# HorsPCB.net
KiCad netlist of a schematic drawn in Altium Designer
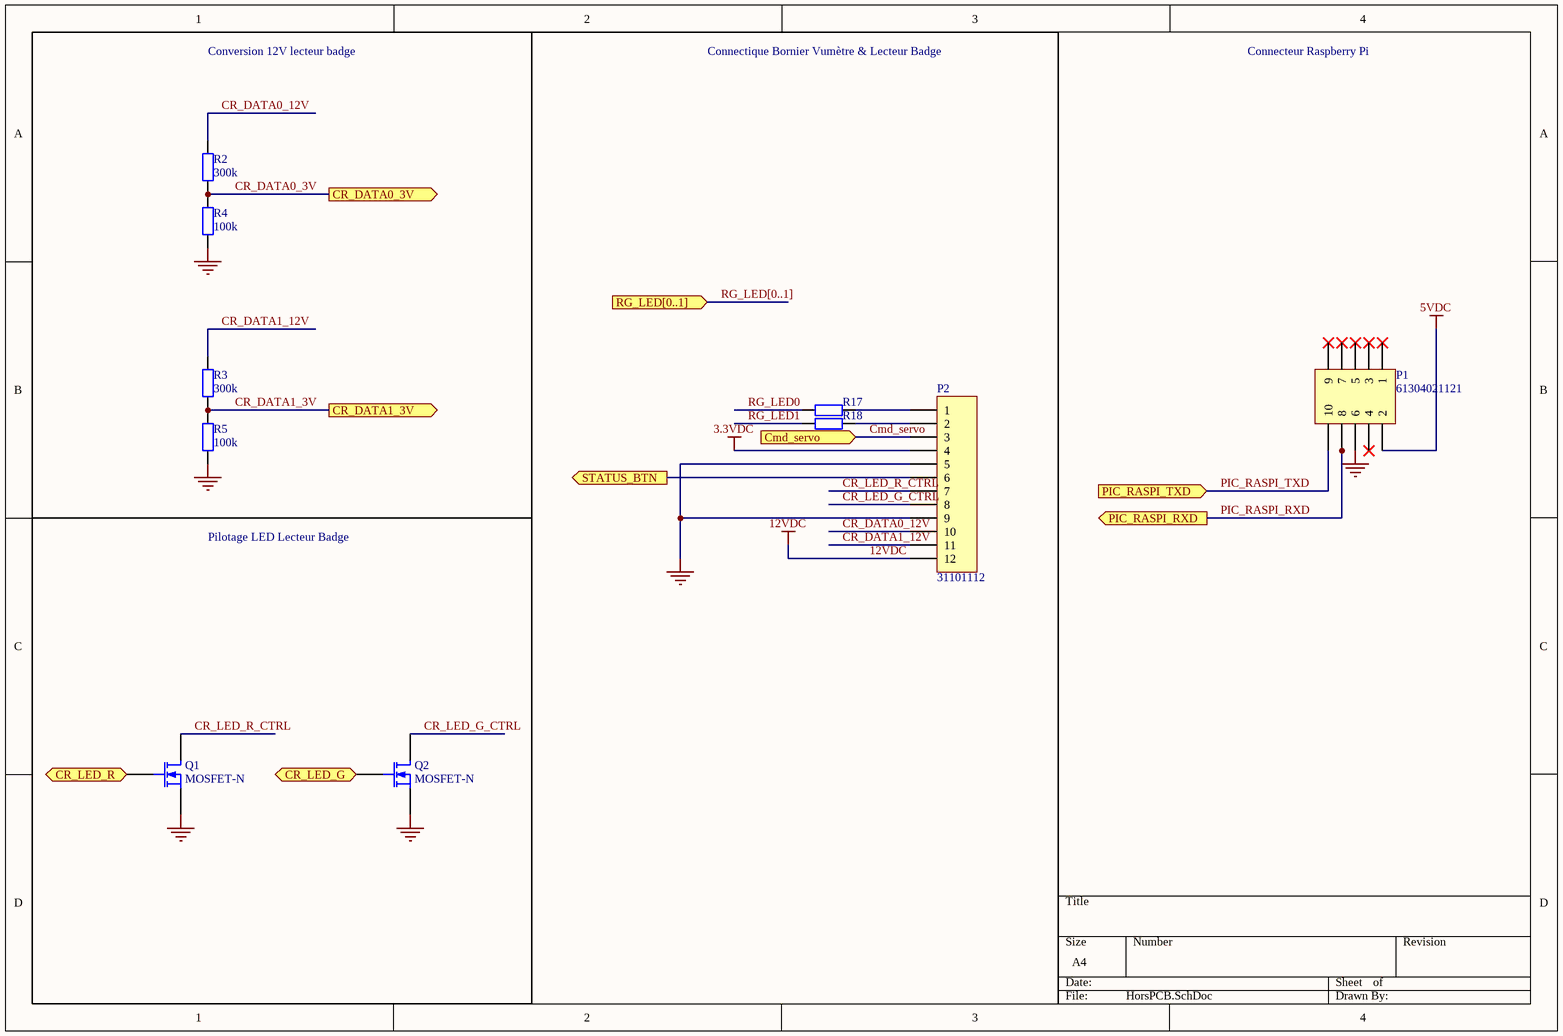
[diagram p0: HorsPCB.SchDoc]

(export (version "E")
  (design (tool "Eeschema 10.0.6"))
  (components
    (comp (ref "P1")
      (value "61304021121")
      (footprint "HDR2X5")
      (description "Header, 5-Pin, Dual row")
      (libsource (lib "Miscellaneous Connectors") (part "Header 5X2"))
    )
    (comp (ref "P2")
      (value "31101112")
      (footprint "Bornier12")
      (description "Header, 12-Pin")
      (libsource (lib "Miscellaneous Connectors") (part "Header 12"))
    )
    (comp (ref "Q1")
      (value "MOSFET-N")
      (footprint "nouveau_mosfetN")
      (description "N-Channel MOSFET")
      (libsource (lib "Miscellaneous Devices") (part "MOSFET-N"))
    )
    (comp (ref "Q2")
      (value "MOSFET-N")
      (footprint "nouveau_mosfetN")
      (description "N-Channel MOSFET")
      (libsource (lib "Miscellaneous Devices") (part "MOSFET-N"))
    )
    (comp (ref "R2")
      (value "300k")
      (footprint "0603")
      (description "Resistor")
      (libsource (lib "Miscellaneous Devices") (part "Res2"))
    )
    (comp (ref "R3")
      (value "300k")
      (footprint "0603")
      (description "Resistor")
      (libsource (lib "Miscellaneous Devices") (part "Res2"))
    )
    (comp (ref "R4")
      (value "100k")
      (footprint "0603")
      (description "Resistor")
      (libsource (lib "Miscellaneous Devices") (part "Res2"))
    )
    (comp (ref "R5")
      (value "100k")
      (footprint "0603")
      (description "Resistor")
      (libsource (lib "Miscellaneous Devices") (part "Res2"))
    )
    (comp (ref "R17")
      (value "60.4")
      (footprint "0603")
      (description "Resistor")
      (libsource (lib "") (part "Res2_1"))
    )
    (comp (ref "R18")
      (value "75")
      (footprint "0603")
      (description "Resistor")
      (libsource (lib "") (part "Res2_1"))
    )
  )
  (nets
    (net (code "1") (name "/CR_DATA0_3V") (class "Default")
      (node (ref "R2") (pin "1") (pinfunction "1_1") (pintype "passive"))
      (node (ref "R4") (pin "2") (pinfunction "2_2") (pintype "passive"))
    )
    (net (code "2") (name "/CR_DATA0_12V") (class "Default")
      (node (ref "P2") (pin "10") (pinfunction "10_10") (pintype "passive"))
      (node (ref "R2") (pin "2") (pinfunction "2_2") (pintype "passive"))
    )
    (net (code "3") (name "/CR_DATA1_3V") (class "Default")
      (node (ref "R3") (pin "1") (pinfunction "1_1") (pintype "passive"))
      (node (ref "R5") (pin "2") (pinfunction "2_2") (pintype "passive"))
    )
    (net (code "4") (name "/CR_DATA1_12V") (class "Default")
      (node (ref "P2") (pin "11") (pinfunction "11_11") (pintype "passive"))
      (node (ref "R3") (pin "2") (pinfunction "2_2") (pintype "passive"))
    )
    (net (code "5") (name "/CR_LED_G") (class "Default")
      (node (ref "Q2") (pin "2") (pinfunction "G_2") (pintype "passive"))
    )
    (net (code "6") (name "/CR_LED_G_CTRL") (class "Default")
      (node (ref "P2") (pin "8") (pinfunction "8_8") (pintype "passive"))
      (node (ref "Q2") (pin "1") (pinfunction "D_1") (pintype "passive"))
    )
    (net (code "7") (name "/CR_LED_R") (class "Default")
      (node (ref "Q1") (pin "2") (pinfunction "G_2") (pintype "passive"))
    )
    (net (code "8") (name "/CR_LED_R_CTRL") (class "Default")
      (node (ref "P2") (pin "7") (pinfunction "7_7") (pintype "passive"))
      (node (ref "Q1") (pin "1") (pinfunction "D_1") (pintype "passive"))
    )
    (net (code "9") (name "/Cmd_servo") (class "Default")
      (node (ref "P2") (pin "3") (pinfunction "3_3") (pintype "passive"))
    )
    (net (code "10") (name "/PIC_RASPI_RXD") (class "Default")
      (node (ref "P1") (pin "8") (pinfunction "8_8") (pintype "passive"))
    )
    (net (code "11") (name "/PIC_RASPI_TXD") (class "Default")
      (node (ref "P1") (pin "10") (pinfunction "10_10") (pintype "passive"))
    )
    (net (code "12") (name "/RG_LED0") (class "Default")
      (node (ref "R17") (pin "1") (pinfunction "1_1") (pintype "passive"))
    )
    (net (code "13") (name "/RG_LED1") (class "Default")
      (node (ref "R18") (pin "1") (pinfunction "1_1") (pintype "passive"))
    )
    (net (code "15") (name "/STATUS_BTN") (class "Default")
      (node (ref "P2") (pin "6") (pinfunction "6_6") (pintype "passive"))
    )
    (net (code "16") (name "3.3VDC") (class "Default")
      (node (ref "P2") (pin "4") (pinfunction "4_4") (pintype "passive"))
    )
    (net (code "17") (name "5VDC") (class "Default")
      (node (ref "P1") (pin "2") (pinfunction "2_2") (pintype "passive"))
    )
    (net (code "18") (name "12VDC") (class "Default")
      (node (ref "P2") (pin "12") (pinfunction "12_12") (pintype "passive"))
    )
    (net (code "19") (name "GND") (class "Default")
      (node (ref "P1") (pin "6") (pinfunction "6_6") (pintype "passive"))
      (node (ref "P2") (pin "5") (pinfunction "5_5") (pintype "passive"))
      (node (ref "P2") (pin "9") (pinfunction "9_9") (pintype "passive"))
      (node (ref "Q1") (pin "3") (pinfunction "S_3") (pintype "passive"))
      (node (ref "Q2") (pin "3") (pinfunction "S_3") (pintype "passive"))
      (node (ref "R4") (pin "1") (pinfunction "1_1") (pintype "passive"))
      (node (ref "R5") (pin "1") (pinfunction "1_1") (pintype "passive"))
    )
    (net (code "20") (name "Net-(P2-Pad1)") (class "Default")
      (node (ref "P2") (pin "1") (pinfunction "1_1") (pintype "passive"))
      (node (ref "R17") (pin "2") (pinfunction "2_2") (pintype "passive"))
    )
    (net (code "21") (name "Net-(P2-Pad2)") (class "Default")
      (node (ref "P2") (pin "2") (pinfunction "2_2") (pintype "passive"))
      (node (ref "R18") (pin "2") (pinfunction "2_2") (pintype "passive"))
    )
    (net (code "22") (name "unconnected-(P1-Pad1)") (class "Default")
      (node (ref "P1") (pin "1") (pinfunction "1_1") (pintype "passive+no_connect"))
    )
    (net (code "23") (name "unconnected-(P1-Pad3)") (class "Default")
      (node (ref "P1") (pin "3") (pinfunction "3_3") (pintype "passive+no_connect"))
    )
    (net (code "24") (name "unconnected-(P1-Pad4)") (class "Default")
      (node (ref "P1") (pin "4") (pinfunction "4_4") (pintype "passive+no_connect"))
    )
    (net (code "25") (name "unconnected-(P1-Pad5)") (class "Default")
      (node (ref "P1") (pin "5") (pinfunction "5_5") (pintype "passive+no_connect"))
    )
    (net (code "26") (name "unconnected-(P1-Pad7)") (class "Default")
      (node (ref "P1") (pin "7") (pinfunction "7_7") (pintype "passive+no_connect"))
    )
    (net (code "27") (name "unconnected-(P1-Pad9)") (class "Default")
      (node (ref "P1") (pin "9") (pinfunction "9_9") (pintype "passive+no_connect"))
    )
  )
)
